# PROC010C_Pwr_RST_LEDs.net
KiCad netlist of a schematic drawn in Altium Designer
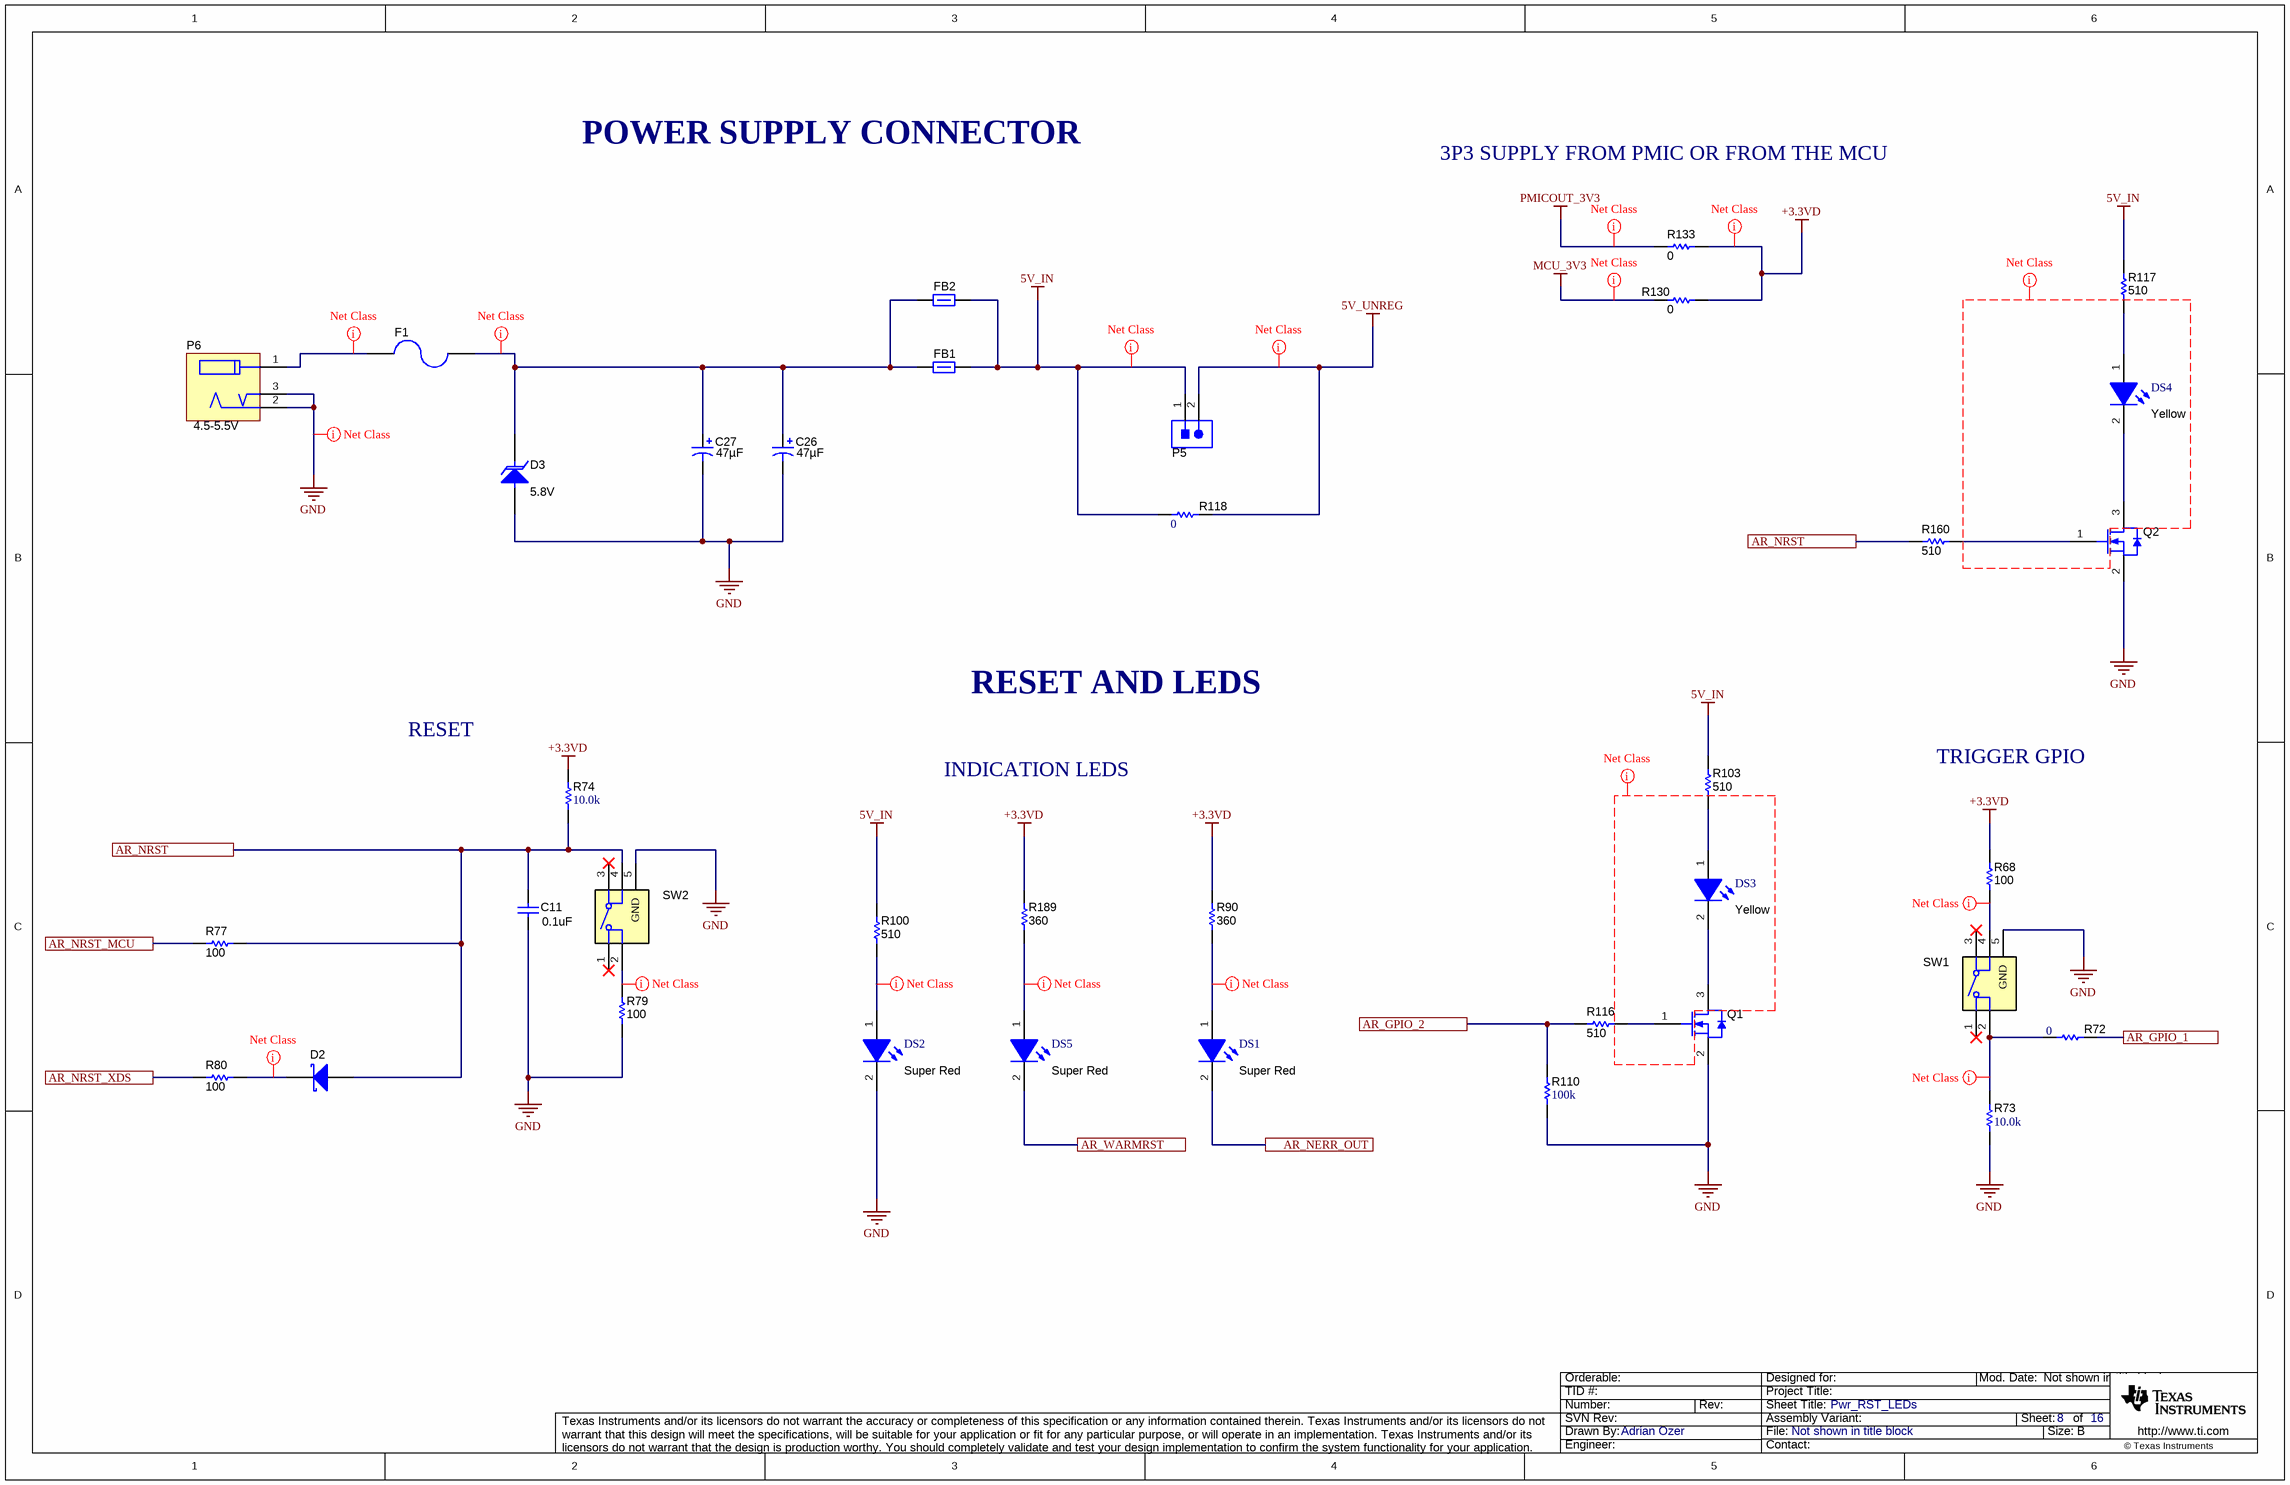
[diagram p0: PROC010C_Pwr_RST_LEDs.SchDoc]

(export (version "E")
  (design (tool "Eeschema 10.0.6"))
  (components
    (comp (ref "C11")
      (value "GCM155R71C104KA55D")
      (footprint "0402L")
      (description "CAP, CERM, 0.1 uF, 16 V, +/- 10%, X7R, 0402")
      (fields
        (field (name "MANUFACTURER") "MuRata")
        (field (name "VALUEDISPLAYED") "0.1uF")
        (field (name "PUBLISHER") "Texas Instruments")
      )
      (libsource (lib "Altium Vault - TI") (part "Capacitor"))
    )
    (comp (ref "C26")
      (value "T491B476K010AT")
      (footprint "3528-21")
      (description "CAP, TA, 47 µF, 10 V, +/- 10%, SMD")
      (fields (field (name "MANUFACTURER") "Kemet") (field (name "VALUEDISPLAYED") "47µF"))
      (libsource (lib "Altium Vault - TI") (part "Cap_Polarized"))
    )
    (comp (ref "C27")
      (value "T491B476K010AT")
      (footprint "3528-21")
      (description "CAP, TA, 47 µF, 10 V, +/- 10%, SMD")
      (fields (field (name "MANUFACTURER") "Kemet") (field (name "VALUEDISPLAYED") "47µF"))
      (libsource (lib "Altium Vault - TI") (part "Cap_Polarized"))
    )
    (comp (ref "D2")
      (value "SMS3923-040LF")
      (footprint "SOD-882")
      (description "Diode, Schottky,  V, 0.01 A, SOD-882")
      (fields (field (name "MANUFACTURER") "Skyworks Solutions"))
      (libsource (lib "Altium Vault - TI") (part "CMP-0078187-1"))
    )
    (comp (ref "D3")
      (value "5.8V")
      (footprint "SMB")
      (description "Diode, TVS, Uni, 5.8 V, 10.5 Vc, AEC-Q101, SMB")
      (fields (field (name "MANUFACTURER") "Littelfuse") (field (name "PARTNUMBER") "SZP6SMB6.8AT3G"))
      (libsource (lib "Altium Vault - TI") (part "Diode_TVS_Uni"))
    )
    (comp (ref "DS1")
      (value "Super Red")
      (footprint "SML-LX0603SRW_SuperRed")
      (description "LED, Super Red, SMD")
      (fields
        (field (name "MANUFACTURER") "Lumex")
        (field (name "PARTNUMBER") "SML-LX0603SRW-TR")
        (field (name "PUBLISHER") "Texas Instruments")
      )
      (libsource (lib "Altium Vault - TI") (part "CMP-0002876-1"))
    )
    (comp (ref "DS2")
      (value "Super Red")
      (footprint "SML-LX0603SRW_SuperRed")
      (description "LED, Super Red, SMD")
      (fields
        (field (name "MANUFACTURER") "Lumex")
        (field (name "PARTNUMBER") "SML-LX0603SRW-TR")
        (field (name "PUBLISHER") "Texas Instruments")
      )
      (libsource (lib "Altium Vault - TI") (part "CMP-0002876-1"))
    )
    (comp (ref "DS3")
      (value "Yellow")
      (footprint "SML-E1_Yellow")
      (description "LED, Yellow, SMD")
      (fields
        (field (name "MANUFACTURER") "Rohm")
        (field (name "PARTNUMBER") "SML-E12Y8WT86")
        (field (name "PUBLISHER") "Texas Instruments")
      )
      (libsource (lib "Altium Vault - TI") (part "LED"))
    )
    (comp (ref "DS4")
      (value "Yellow")
      (footprint "SML-E1_Yellow")
      (description "LED, Yellow, SMD")
      (fields
        (field (name "MANUFACTURER") "Rohm")
        (field (name "PARTNUMBER") "SML-E12Y8WT86")
        (field (name "PUBLISHER") "Texas Instruments")
      )
      (libsource (lib "Altium Vault - TI") (part "CMP-0002977-2"))
    )
    (comp (ref "DS5")
      (value "Super Red")
      (footprint "SML-LX0603SRW_SuperRed")
      (description "LED, Super Red, SMD")
      (fields
        (field (name "MANUFACTURER") "Lumex")
        (field (name "PARTNUMBER") "SML-LX0603SRW-TR")
        (field (name "PUBLISHER") "Texas Instruments")
      )
      (libsource (lib "Altium Vault - TI") (part "CMP-0002876-1"))
    )
    (comp (ref "F1")
      (value "0440005.WR")
      (footprint "1206")
      (description "Fuse, 5 A, 32VAC/VDC, SMD")
      (fields (field (name "MANUFACTURER") "Littelfuse"))
      (libsource (lib "Altium Vault - TI") (part "Fuse"))
    )
    (comp (ref "FB1")
      (value "BLM21PG300SH1D")
      (footprint "0805_HV")
      (description "Ferrite Bead, 30 ohm @ 100 MHz, 4 A, 0805")
      (fields (field (name "MANUFACTURER") "MuRata") (field (name "PUBLISHER") "Texas Instruments"))
      (libsource (lib "Altium Vault - TI") (part "CMP-0003364-1"))
    )
    (comp (ref "FB2")
      (value "BLM21PG300SH1D")
      (footprint "0805_HV")
      (description "Ferrite Bead, 30 ohm @ 100 MHz, 4 A, 0805")
      (fields (field (name "MANUFACTURER") "MuRata") (field (name "PUBLISHER") "Texas Instruments"))
      (libsource (lib "Altium Vault - TI") (part "CMP-0003364-1"))
    )
    (comp (ref "P5")
      (value "TSW-102-07-G-S")
      (footprint "TSW-102-07-G-S")
      (description "Header, 100mil, 2x1, Gold, TH")
      (fields (field (name "MANUFACTURER") "Samtec"))
      (libsource (lib "Altium Vault - TI") (part "Header_2x1"))
    )
    (comp (ref "P6")
      (value "PJ-002AH")
      (footprint "CUI_PJ-002AH")
      (description "DC POWER JACK, R/A, TH")
      (fields (field (name "VOLTAGE_V") "4.5-5.5V") (field (name "MANUFACTURER") "CUI Inc."))
      (libsource (lib "Altium Vault - TI") (part "CONN_DC JACK"))
    )
    (comp (ref "Q1")
      (value "BSS123")
      (footprint "SOT-23")
      (description "MOSFET, N-CH, 100 V, 0.17 A, SOT-23")
      (fields
        (field (name "MANUFACTURER") "Fairchild Semiconductor")
        (field (name "PUBLISHER") "Texas Instruments")
      )
      (libsource (lib "Altium Vault - TI") (part "MOSFET_N_D3G1S2"))
    )
    (comp (ref "Q2")
      (value "BSS123")
      (footprint "SOT-23")
      (description "MOSFET, N-CH, 100 V, 0.17 A, SOT-23")
      (fields
        (field (name "MANUFACTURER") "Fairchild Semiconductor")
        (field (name "PUBLISHER") "Texas Instruments")
      )
      (libsource (lib "Altium Vault - TI") (part "MOSFET_N_D3G1S2"))
    )
    (comp (ref "R68")
      (value "ERJ-2GEJ101X")
      (footprint "0402L")
      (description "RES, 100, 5%, 0.1 W, AEC-Q200 Grade 0, 0402")
      (fields
        (field (name "MANUFACTURER") "Panasonic")
        (field (name "VALUEDISPLAYED") "100")
        (field (name "PUBLISHER") "Texas Instruments")
      )
      (libsource (lib "Altium Vault - TI") (part "Resistor"))
    )
    (comp (ref "R72")
      (value "CRCW02010000Z0ED")
      (footprint "0201_Silk")
      (description "RES, 0, 5%, 0.05 W, 0201")
      (fields (field (name "MANUFACTURER") "Vishay-Dale") (field (name "VALUEDISPLAYED") "0"))
      (libsource (lib "Altium Vault - TI") (part "Resistor"))
    )
    (comp (ref "R73")
      (value "CRCW040210K0FKED")
      (footprint "0402L")
      (description "RES, 10.0 k, 1%, 0.063 W, AEC-Q200 Grade 0, 0402")
      (fields (field (name "MANUFACTURER") "Vishay-Dale") (field (name "VALUEDISPLAYED") "10.0k"))
      (libsource (lib "Altium Vault - TI") (part "Resistor"))
    )
    (comp (ref "R74")
      (value "CRCW040210K0FKED")
      (footprint "0402L")
      (description "RES, 10.0 k, 1%, 0.063 W, AEC-Q200 Grade 0, 0402")
      (fields (field (name "MANUFACTURER") "Vishay-Dale") (field (name "VALUEDISPLAYED") "10.0k"))
      (libsource (lib "Altium Vault - TI") (part "Resistor"))
    )
    (comp (ref "R77")
      (value "ERJ-2GEJ101X")
      (footprint "0402L")
      (description "RES, 100, 5%, 0.1 W, AEC-Q200 Grade 0, 0402")
      (fields
        (field (name "MANUFACTURER") "Panasonic")
        (field (name "VALUEDISPLAYED") "100")
        (field (name "PUBLISHER") "Texas Instruments")
      )
      (libsource (lib "Altium Vault - TI") (part "Resistor"))
    )
    (comp (ref "R79")
      (value "ERJ-2GEJ101X")
      (footprint "0402L")
      (description "RES, 100, 5%, 0.1 W, AEC-Q200 Grade 0, 0402")
      (fields
        (field (name "MANUFACTURER") "Panasonic")
        (field (name "VALUEDISPLAYED") "100")
        (field (name "PUBLISHER") "Texas Instruments")
      )
      (libsource (lib "Altium Vault - TI") (part "Resistor"))
    )
    (comp (ref "R80")
      (value "ERJ-2GEJ101X")
      (footprint "0402L")
      (description "RES, 100, 5%, 0.1 W, AEC-Q200 Grade 0, 0402")
      (fields
        (field (name "MANUFACTURER") "Panasonic")
        (field (name "VALUEDISPLAYED") "100")
        (field (name "PUBLISHER") "Texas Instruments")
      )
      (libsource (lib "Altium Vault - TI") (part "Resistor"))
    )
    (comp (ref "R90")
      (value "ERJ-2GEJ361X")
      (footprint "0402L")
      (description "RES, 360, 5%, 0.1 W, AEC-Q200 Grade 0, 0402")
      (fields (field (name "MANUFACTURER") "Panasonic") (field (name "VALUEDISPLAYED") "360"))
      (libsource (lib "Altium Vault - TI") (part "Resistor"))
    )
    (comp (ref "R100")
      (value "ERJ-2GEJ511X")
      (footprint "0402L")
      (description "RES, 510, 5%, 0.1 W, AEC-Q200 Grade 0, 0402")
      (fields (field (name "MANUFACTURER") "Panasonic") (field (name "VALUEDISPLAYED") "510"))
      (libsource (lib "Altium Vault - TI") (part "Resistor"))
    )
    (comp (ref "R103")
      (value "ERJ-2GEJ511X")
      (footprint "0402L")
      (description "RES, 510, 5%, 0.1 W, AEC-Q200 Grade 0, 0402")
      (fields (field (name "MANUFACTURER") "Panasonic") (field (name "VALUEDISPLAYED") "510"))
      (libsource (lib "Altium Vault - TI") (part "Resistor"))
    )
    (comp (ref "R110")
      (value "CRCW0402100KFKED")
      (footprint "0402L")
      (description "RES, 100 k, 1%, 0.063 W, AEC-Q200 Grade 0, 0402")
      (fields (field (name "MANUFACTURER") "Vishay-Dale") (field (name "VALUEDISPLAYED") "100k"))
      (libsource (lib "Altium Vault - TI") (part "Resistor"))
    )
    (comp (ref "R116")
      (value "ERJ-2GEJ511X")
      (footprint "0402L")
      (description "RES, 510, 5%, 0.1 W, AEC-Q200 Grade 0, 0402")
      (fields (field (name "MANUFACTURER") "Panasonic") (field (name "VALUEDISPLAYED") "510"))
      (libsource (lib "Altium Vault - TI") (part "Resistor"))
    )
    (comp (ref "R117")
      (value "ERJ-2GEJ511X")
      (footprint "0402L")
      (description "RES, 510, 5%, 0.1 W, AEC-Q200 Grade 0, 0402")
      (fields (field (name "MANUFACTURER") "Panasonic") (field (name "VALUEDISPLAYED") "510"))
      (libsource (lib "Altium Vault - TI") (part "Resistor"))
    )
    (comp (ref "R118")
      (value "CRCW20100000Z0EF")
      (footprint "2010")
      (description "RES, 0, 5%, 0.75 W, AEC-Q200 Grade 0, 2010")
      (fields (field (name "MANUFACTURER") "Vishay-Dale") (field (name "VALUEDISPLAYED") "0"))
      (libsource (lib "Altium Vault - TI") (part "Resistor"))
    )
    (comp (ref "R130")
      (value "MCT06030Z0000ZP500")
      (footprint "0603")
      (description "RES, 0, 5%, 0.125 W, 0603")
      (fields
        (field (name "MANUFACTURER") "Vishay/Beyschlag")
        (field (name "VALUEDISPLAYED") "0")
        (field (name "PUBLISHER") "Texas Instruments")
      )
      (libsource (lib "Altium Vault - TI") (part "CMP-0025884-3"))
    )
    (comp (ref "R133")
      (value "MCT06030Z0000ZP500")
      (footprint "0603")
      (description "RES, 0, 5%, 0.125 W, 0603")
      (fields
        (field (name "MANUFACTURER") "Vishay/Beyschlag")
        (field (name "VALUEDISPLAYED") "0")
        (field (name "PUBLISHER") "Texas Instruments")
      )
      (libsource (lib "Altium Vault - TI") (part "Resistor"))
    )
    (comp (ref "R160")
      (value "ERJ-2GEJ511X")
      (footprint "0402L")
      (description "RES, 510, 5%, 0.1 W, AEC-Q200 Grade 0, 0402")
      (fields (field (name "MANUFACTURER") "Panasonic") (field (name "VALUEDISPLAYED") "510"))
      (libsource (lib "Altium Vault - TI") (part "Resistor"))
    )
    (comp (ref "R189")
      (value "ERJ-2GEJ361X")
      (footprint "0402L")
      (description "RES, 360, 5%, 0.1 W, AEC-Q200 Grade 0, 0402")
      (fields (field (name "MANUFACTURER") "Panasonic") (field (name "VALUEDISPLAYED") "360"))
      (libsource (lib "Altium Vault - TI") (part "Resistor"))
    )
    (comp (ref "SW1")
      (value "KMR243GLFG")
      (footprint "SW_KMR243GLFG")
      (description "Switch, SPST-NO, Off-Mom, 0.01 A, 32 VDC, SMD")
      (fields (field (name "MANUFACTURER") "C&K Components") (field (name "PUBLISHER") "Texas Instruments"))
      (libsource (lib "Altium Vault - TI") (part "CMP-0002325-1"))
    )
    (comp (ref "SW2")
      (value "KMR243GLFG")
      (footprint "SW_KMR243GLFG")
      (description "Switch, SPST-NO, Off-Mom, 0.01 A, 32 VDC, SMD")
      (fields (field (name "MANUFACTURER") "C&K Components") (field (name "PUBLISHER") "Texas Instruments"))
      (libsource (lib "Altium Vault - TI") (part "CMP-0002325-1"))
    )
  )
  (nets
    (net (code "1") (name "+3.3VD") (class "Default")
      (node (ref "R130") (pin "2") (pinfunction "2_2") (pintype "passive"))
      (node (ref "R133") (pin "2") (pinfunction "2_2") (pintype "passive"))
      (node (ref "R189") (pin "2") (pinfunction "2_2") (pintype "passive"))
      (node (ref "R68") (pin "2") (pinfunction "2_2") (pintype "passive"))
      (node (ref "R74") (pin "2") (pinfunction "2_2") (pintype "passive"))
      (node (ref "R90") (pin "2") (pinfunction "2_2") (pintype "passive"))
    )
    (net (code "2") (name "/AR_GPIO_1") (class "Default")
      (node (ref "R72") (pin "2") (pinfunction "2_2") (pintype "passive"))
    )
    (net (code "3") (name "/AR_GPIO_2") (class "Default")
      (node (ref "R110") (pin "2") (pinfunction "2_2") (pintype "passive"))
      (node (ref "R116") (pin "1") (pinfunction "1_1") (pintype "passive"))
    )
    (net (code "4") (name "/AR_NERR_OUT") (class "Default")
      (node (ref "DS1") (pin "2") (pinfunction "K_2") (pintype "passive"))
    )
    (net (code "5") (name "/AR_NRST") (class "Default")
      (node (ref "C11") (pin "2") (pinfunction "2_2") (pintype "passive"))
      (node (ref "D2") (pin "2") (pinfunction "A_2") (pintype "passive"))
      (node (ref "R160") (pin "1") (pinfunction "1_1") (pintype "passive"))
      (node (ref "R74") (pin "1") (pinfunction "1_1") (pintype "passive"))
      (node (ref "R77") (pin "2") (pinfunction "2_2") (pintype "passive"))
      (node (ref "SW2") (pin "4") (pinfunction "4_4") (pintype "passive"))
    )
    (net (code "6") (name "/AR_NRST_MCU") (class "Default")
      (node (ref "R77") (pin "1") (pinfunction "1_1") (pintype "passive"))
    )
    (net (code "7") (name "/AR_NRST_XDS") (class "Default")
      (node (ref "R80") (pin "1") (pinfunction "1_1") (pintype "passive"))
    )
    (net (code "8") (name "/AR_WARMRST") (class "Default")
      (node (ref "DS5") (pin "2") (pinfunction "K_2") (pintype "passive"))
    )
    (net (code "9") (name "5V_IN") (class "Default")
      (node (ref "FB1") (pin "2") (pinfunction "2_2") (pintype "passive"))
      (node (ref "FB2") (pin "2") (pinfunction "2_2") (pintype "passive"))
      (node (ref "P5") (pin "1") (pinfunction "1_1") (pintype "passive"))
      (node (ref "R100") (pin "2") (pinfunction "2_2") (pintype "passive"))
      (node (ref "R103") (pin "2") (pinfunction "2_2") (pintype "passive"))
      (node (ref "R117") (pin "2") (pinfunction "2_2") (pintype "passive"))
      (node (ref "R118") (pin "1") (pinfunction "1_1") (pintype "passive"))
    )
    (net (code "10") (name "5V_UNREG") (class "Default")
      (node (ref "P5") (pin "2") (pinfunction "2_2") (pintype "passive"))
      (node (ref "R118") (pin "2") (pinfunction "2_2") (pintype "passive"))
    )
    (net (code "11") (name "GND") (class "Default")
      (node (ref "C11") (pin "1") (pinfunction "1_1") (pintype "passive"))
      (node (ref "C26") (pin "2") (pinfunction "-_2") (pintype "passive"))
      (node (ref "C27") (pin "2") (pinfunction "-_2") (pintype "passive"))
      (node (ref "D3") (pin "2") (pinfunction "A_2") (pintype "passive"))
      (node (ref "DS2") (pin "2") (pinfunction "K_2") (pintype "passive"))
      (node (ref "P6") (pin "2") (pinfunction "2_2") (pintype "passive"))
      (node (ref "P6") (pin "3") (pinfunction "3_3") (pintype "passive"))
      (node (ref "Q1") (pin "2") (pinfunction "S_2") (pintype "passive"))
      (node (ref "Q2") (pin "2") (pinfunction "S_2") (pintype "passive"))
      (node (ref "R110") (pin "1") (pinfunction "1_1") (pintype "passive"))
      (node (ref "R73") (pin "1") (pinfunction "1_1") (pintype "passive"))
      (node (ref "R79") (pin "1") (pinfunction "1_1") (pintype "passive"))
      (node (ref "SW1") (pin "5") (pinfunction "GND_5") (pintype "passive"))
      (node (ref "SW2") (pin "5") (pinfunction "GND_5") (pintype "passive"))
    )
    (net (code "12") (name "MCU_3V3") (class "Default")
      (node (ref "R130") (pin "1") (pinfunction "1_1") (pintype "passive"))
    )
    (net (code "13") (name "Net-(C26-+)") (class "Default")
      (node (ref "C26") (pin "1") (pinfunction "+_1") (pintype "passive"))
      (node (ref "C27") (pin "1") (pinfunction "+_1") (pintype "passive"))
      (node (ref "D3") (pin "1") (pinfunction "K_1") (pintype "passive"))
      (node (ref "F1") (pin "1") (pinfunction "1_1") (pintype "passive"))
      (node (ref "FB1") (pin "1") (pinfunction "1_1") (pintype "passive"))
      (node (ref "FB2") (pin "1") (pinfunction "1_1") (pintype "passive"))
    )
    (net (code "14") (name "Net-(D2-K)") (class "Default")
      (node (ref "D2") (pin "1") (pinfunction "K_1") (pintype "passive"))
      (node (ref "R80") (pin "2") (pinfunction "2_2") (pintype "passive"))
    )
    (net (code "15") (name "Net-(DS1-A)") (class "Default")
      (node (ref "DS1") (pin "1") (pinfunction "A_1") (pintype "passive"))
      (node (ref "R90") (pin "1") (pinfunction "1_1") (pintype "passive"))
    )
    (net (code "16") (name "Net-(DS2-A)") (class "Default")
      (node (ref "DS2") (pin "1") (pinfunction "A_1") (pintype "passive"))
      (node (ref "R100") (pin "1") (pinfunction "1_1") (pintype "passive"))
    )
    (net (code "17") (name "Net-(DS3-A)") (class "Default")
      (node (ref "DS3") (pin "1") (pinfunction "A_1") (pintype "passive"))
      (node (ref "R103") (pin "1") (pinfunction "1_1") (pintype "passive"))
    )
    (net (code "18") (name "Net-(DS3-K)") (class "Default")
      (node (ref "DS3") (pin "2") (pinfunction "K_2") (pintype "passive"))
      (node (ref "Q1") (pin "3") (pinfunction "D_3") (pintype "passive"))
    )
    (net (code "19") (name "Net-(DS4-A)") (class "Default")
      (node (ref "DS4") (pin "1") (pinfunction "A_1") (pintype "passive"))
      (node (ref "R117") (pin "1") (pinfunction "1_1") (pintype "passive"))
    )
    (net (code "20") (name "Net-(DS4-K)") (class "Default")
      (node (ref "DS4") (pin "2") (pinfunction "K_2") (pintype "passive"))
      (node (ref "Q2") (pin "3") (pinfunction "D_3") (pintype "passive"))
    )
    (net (code "21") (name "Net-(DS5-A)") (class "Default")
      (node (ref "DS5") (pin "1") (pinfunction "A_1") (pintype "passive"))
      (node (ref "R189") (pin "1") (pinfunction "1_1") (pintype "passive"))
    )
    (net (code "22") (name "Net-(F1-Pad2)") (class "Default")
      (node (ref "F1") (pin "2") (pinfunction "2_2") (pintype "passive"))
      (node (ref "P6") (pin "1") (pinfunction "1_1") (pintype "passive"))
    )
    (net (code "23") (name "Net-(Q1-G)") (class "Default")
      (node (ref "Q1") (pin "1") (pinfunction "G_1") (pintype "passive"))
      (node (ref "R116") (pin "2") (pinfunction "2_2") (pintype "passive"))
    )
    (net (code "24") (name "Net-(Q2-G)") (class "Default")
      (node (ref "Q2") (pin "1") (pinfunction "G_1") (pintype "passive"))
      (node (ref "R160") (pin "2") (pinfunction "2_2") (pintype "passive"))
    )
    (net (code "25") (name "Net-(R68-Pad1)") (class "Default")
      (node (ref "R68") (pin "1") (pinfunction "1_1") (pintype "passive"))
      (node (ref "SW1") (pin "4") (pinfunction "4_4") (pintype "passive"))
    )
    (net (code "26") (name "Net-(R72-Pad1)") (class "Default")
      (node (ref "R72") (pin "1") (pinfunction "1_1") (pintype "passive"))
      (node (ref "R73") (pin "2") (pinfunction "2_2") (pintype "passive"))
      (node (ref "SW1") (pin "2") (pinfunction "2_2") (pintype "passive"))
    )
    (net (code "27") (name "Net-(R79-Pad2)") (class "Default")
      (node (ref "R79") (pin "2") (pinfunction "2_2") (pintype "passive"))
      (node (ref "SW2") (pin "2") (pinfunction "2_2") (pintype "passive"))
    )
    (net (code "28") (name "PMICOUT_3V3") (class "Default")
      (node (ref "R133") (pin "1") (pinfunction "1_1") (pintype "passive"))
    )
    (net (code "29") (name "unconnected-(SW1-Pad1)") (class "Default")
      (node (ref "SW1") (pin "1") (pinfunction "1_1") (pintype "passive+no_connect"))
    )
    (net (code "30") (name "unconnected-(SW1-Pad3)") (class "Default")
      (node (ref "SW1") (pin "3") (pinfunction "3_3") (pintype "passive+no_connect"))
    )
    (net (code "31") (name "unconnected-(SW2-Pad1)") (class "Default")
      (node (ref "SW2") (pin "1") (pinfunction "1_1") (pintype "passive+no_connect"))
    )
    (net (code "32") (name "unconnected-(SW2-Pad3)") (class "Default")
      (node (ref "SW2") (pin "3") (pinfunction "3_3") (pintype "passive+no_connect"))
    )
  )
)
